# LPC_Rep.net
KiCad netlist of a schematic drawn in Altium Designer
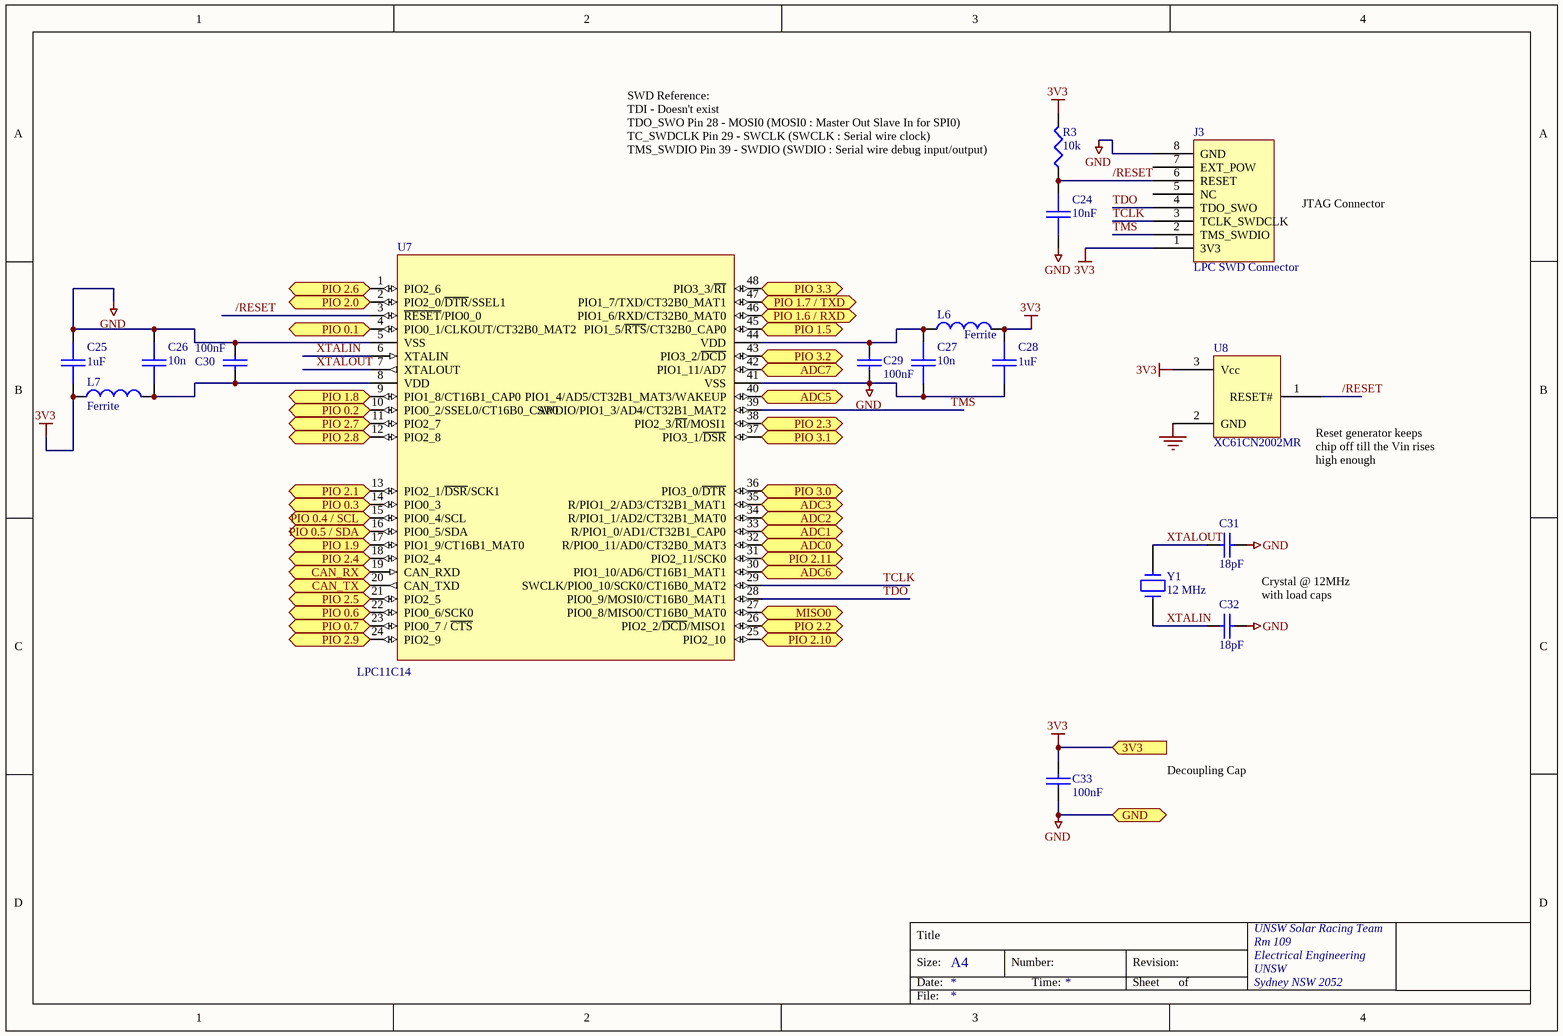
[diagram p0: LPC_Rep.SchDoc]

(export (version "E")
  (design (tool "Eeschema 10.0.6"))
  (components
    (comp (ref "C24")
      (value "10nF")
      (footprint "0603")
      (description "Capacitor")
      (libsource (lib "SunswiftLib20030312RR") (part "CAP"))
    )
    (comp (ref "C25")
      (value "1uF")
      (footprint "0603")
      (description "Capacitor")
      (fields (field (name "Comment") "1u"))
      (libsource (lib "RCLDQ") (part "CAP"))
    )
    (comp (ref "C26")
      (value "10n")
      (footprint "0603")
      (description "Capacitor")
      (libsource (lib "2009_BatteryMaster") (part "CAP"))
    )
    (comp (ref "C27")
      (value "10n")
      (footprint "0603")
      (description "Capacitor")
      (libsource (lib "2009_BatteryMaster") (part "CAP"))
    )
    (comp (ref "C28")
      (value "1uF")
      (footprint "0603")
      (description "Capacitor")
      (fields (field (name "Comment") "1u"))
      (libsource (lib "RCLDQ") (part "CAP"))
    )
    (comp (ref "C29")
      (value "100nF")
      (footprint "0603")
      (description "Capacitor")
      (libsource (lib "*") (part "CAP"))
    )
    (comp (ref "C30")
      (value "100nF")
      (footprint "0603")
      (description "Capacitor")
      (libsource (lib "*") (part "CAP"))
    )
    (comp (ref "C31")
      (value "18pF")
      (footprint "0603")
      (description "Capacitor")
      (libsource (lib "*") (part "CAP"))
    )
    (comp (ref "C32")
      (value "18pF")
      (footprint "0603")
      (description "Capacitor")
      (libsource (lib "*") (part "CAP"))
    )
    (comp (ref "C33")
      (value "100nF")
      (footprint "0603")
      (description "Capacitor")
      (libsource (lib "*") (part "CAP"))
    )
    (comp (ref "J3")
      (value "LPC SWD Connector")
      (footprint "IDC8")
      (libsource (lib "2009_BatteryMaster") (part "LPCLink_Connector"))
    )
    (comp (ref "L6")
      (value "Ferrite")
      (footprint "0603")
      (description "Inductor")
      (fields (field (name "MANUFACTURER") "Generic Components") (field (name "PUBLISHER") "Altium Limited"))
      (libsource (lib "RCLDQ") (part "INDUCTOR"))
    )
    (comp (ref "L7")
      (value "Ferrite")
      (footprint "0603")
      (description "Inductor")
      (fields (field (name "MANUFACTURER") "Generic Components") (field (name "PUBLISHER") "Altium Limited"))
      (libsource (lib "RCLDQ") (part "INDUCTOR"))
    )
    (comp (ref "R3")
      (value "10k")
      (footprint "0603")
      (description "Resistor")
      (libsource (lib "SunswiftLib20030312RR") (part "RES1"))
    )
    (comp (ref "U7")
      (value "LPC11C14")
      (footprint "TSQFP50P900X900-48N")
      (libsource (lib "LPC") (part "LPC11C14_Full"))
    )
    (comp (ref "U8")
      (value "XC61CN2002MR")
      (footprint "SOT23(3)")
      (description "SOT23 reset generator")
      (libsource (lib "*") (part "XC61F"))
    )
    (comp (ref "Y1")
      (value "12 MHz")
      (footprint "HC49/4H")
      (description "Crystal")
      (libsource (lib "*") (part "CRYSTAL"))
    )
  )
  (nets
    (net (code "1") (name "/ADC0") (class "Default")
      (node (ref "U7") (pin "32") (pinfunction "R/PIO0_11/AD0/CT32B0_MAT3_32") (pintype "bidirectional"))
    )
    (net (code "2") (name "/ADC1") (class "Default")
      (node (ref "U7") (pin "33") (pinfunction "R/PIO1_0/AD1/CT32B1_CAP0_33") (pintype "bidirectional"))
    )
    (net (code "3") (name "/ADC2") (class "Default")
      (node (ref "U7") (pin "34") (pinfunction "R/PIO1_1/AD2/CT32B1_MAT0_34") (pintype "bidirectional"))
    )
    (net (code "4") (name "/ADC3") (class "Default")
      (node (ref "U7") (pin "35") (pinfunction "R/PIO1_2/AD3/CT32B1_MAT1_35") (pintype "bidirectional"))
    )
    (net (code "5") (name "/ADC5") (class "Default")
      (node (ref "U7") (pin "40") (pinfunction "PIO1_4/AD5/CT32B1_MAT3/WAKEUP_40") (pintype "bidirectional"))
    )
    (net (code "6") (name "/ADC6") (class "Default")
      (node (ref "U7") (pin "30") (pinfunction "PIO1_10/AD6/CT16B1_MAT1_30") (pintype "bidirectional"))
    )
    (net (code "7") (name "/ADC7") (class "Default")
      (node (ref "U7") (pin "42") (pinfunction "PIO1_11/AD7_42") (pintype "bidirectional"))
    )
    (net (code "8") (name "/CAN_RX") (class "Default")
      (node (ref "U7") (pin "19") (pinfunction "CAN_RXD_19") (pintype "input"))
    )
    (net (code "9") (name "/CAN_TX") (class "Default")
      (node (ref "U7") (pin "20") (pinfunction "CAN_TXD_20") (pintype "output"))
    )
    (net (code "10") (name "/MISO0") (class "Default")
      (node (ref "U7") (pin "27") (pinfunction "PIO0_8/MISO0/CT16B0_MAT0_27") (pintype "bidirectional"))
    )
    (net (code "11") (name "/PIO 0.1") (class "Default")
      (node (ref "U7") (pin "4") (pinfunction "PIO0_1/CLKOUT/CT32B0_MAT2_4") (pintype "bidirectional"))
    )
    (net (code "12") (name "/PIO 0.2") (class "Default")
      (node (ref "U7") (pin "10") (pinfunction "PIO0_2/SSEL0/CT16B0_CAP0_10") (pintype "bidirectional"))
    )
    (net (code "13") (name "/PIO 0.3") (class "Default")
      (node (ref "U7") (pin "14") (pinfunction "PIO0_3_14") (pintype "bidirectional"))
    )
    (net (code "14") (name "/PIO 0.4 {slash} SCL") (class "Default")
      (node (ref "U7") (pin "15") (pinfunction "PIO0_4/SCL_15") (pintype "bidirectional"))
    )
    (net (code "15") (name "/PIO 0.5 {slash} SDA") (class "Default")
      (node (ref "U7") (pin "16") (pinfunction "PIO0_5/SDA_16") (pintype "bidirectional"))
    )
    (net (code "16") (name "/PIO 0.6") (class "Default")
      (node (ref "U7") (pin "22") (pinfunction "PIO0_6/SCK0_22") (pintype "bidirectional"))
    )
    (net (code "17") (name "/PIO 0.7") (class "Default")
      (node (ref "U7") (pin "23") (pinfunction "PIO0_7_/_~{CTS}_23") (pintype "bidirectional"))
    )
    (net (code "18") (name "/PIO 1.5") (class "Default")
      (node (ref "U7") (pin "45") (pinfunction "PIO1_5/~{RTS}/CT32B0_CAP0_45") (pintype "bidirectional"))
    )
    (net (code "19") (name "/PIO 1.6 {slash} RXD") (class "Default")
      (node (ref "U7") (pin "46") (pinfunction "PIO1_6/RXD/CT32B0_MAT0_46") (pintype "bidirectional"))
    )
    (net (code "20") (name "/PIO 1.7 {slash} TXD") (class "Default")
      (node (ref "U7") (pin "47") (pinfunction "PIO1_7/TXD/CT32B0_MAT1_47") (pintype "bidirectional"))
    )
    (net (code "21") (name "/PIO 1.8") (class "Default")
      (node (ref "U7") (pin "9") (pinfunction "PIO1_8/CT16B1_CAP0_9") (pintype "bidirectional"))
    )
    (net (code "22") (name "/PIO 1.9") (class "Default")
      (node (ref "U7") (pin "17") (pinfunction "PIO1_9/CT16B1_MAT0_17") (pintype "bidirectional"))
    )
    (net (code "23") (name "/PIO 2.0") (class "Default")
      (node (ref "U7") (pin "2") (pinfunction "PIO2_0/~{DTR}/SSEL1_2") (pintype "bidirectional"))
    )
    (net (code "24") (name "/PIO 2.1") (class "Default")
      (node (ref "U7") (pin "13") (pinfunction "PIO2_1/~{DSR}/SCK1_13") (pintype "bidirectional"))
    )
    (net (code "25") (name "/PIO 2.2") (class "Default")
      (node (ref "U7") (pin "26") (pinfunction "PIO2_2/~{DCD}/MISO1_26") (pintype "bidirectional"))
    )
    (net (code "26") (name "/PIO 2.3") (class "Default")
      (node (ref "U7") (pin "38") (pinfunction "PIO2_3/~{RI}/MOSI1_38") (pintype "bidirectional"))
    )
    (net (code "27") (name "/PIO 2.4") (class "Default")
      (node (ref "U7") (pin "18") (pinfunction "PIO2_4_18") (pintype "bidirectional"))
    )
    (net (code "28") (name "/PIO 2.5") (class "Default")
      (node (ref "U7") (pin "21") (pinfunction "PIO2_5_21") (pintype "bidirectional"))
    )
    (net (code "29") (name "/PIO 2.6") (class "Default")
      (node (ref "U7") (pin "1") (pinfunction "PIO2_6_1") (pintype "bidirectional"))
    )
    (net (code "30") (name "/PIO 2.7") (class "Default")
      (node (ref "U7") (pin "11") (pinfunction "PIO2_7_11") (pintype "bidirectional"))
    )
    (net (code "31") (name "/PIO 2.8") (class "Default")
      (node (ref "U7") (pin "12") (pinfunction "PIO2_8_12") (pintype "bidirectional"))
    )
    (net (code "32") (name "/PIO 2.9") (class "Default")
      (node (ref "U7") (pin "24") (pinfunction "PIO2_9_24") (pintype "bidirectional"))
    )
    (net (code "33") (name "/PIO 2.10") (class "Default")
      (node (ref "U7") (pin "25") (pinfunction "PIO2_10_25") (pintype "bidirectional"))
    )
    (net (code "34") (name "/PIO 2.11") (class "Default")
      (node (ref "U7") (pin "31") (pinfunction "PIO2_11/SCK0_31") (pintype "bidirectional"))
    )
    (net (code "35") (name "/PIO 3.0") (class "Default")
      (node (ref "U7") (pin "36") (pinfunction "PIO3_0/~{DTR}_36") (pintype "bidirectional"))
    )
    (net (code "36") (name "/PIO 3.1") (class "Default")
      (node (ref "U7") (pin "37") (pinfunction "PIO3_1/~{DSR}_37") (pintype "bidirectional"))
    )
    (net (code "37") (name "/PIO 3.2") (class "Default")
      (node (ref "U7") (pin "43") (pinfunction "PIO3_2/~{DCD}_43") (pintype "bidirectional"))
    )
    (net (code "38") (name "/PIO 3.3") (class "Default")
      (node (ref "U7") (pin "48") (pinfunction "PIO3_3/~{RI}_48") (pintype "bidirectional"))
    )
    (net (code "39") (name "/TCLK") (class "Default")
      (node (ref "J3") (pin "3") (pinfunction "TCLK_SWDCLK_3") (pintype "passive"))
      (node (ref "U7") (pin "29") (pinfunction "SWCLK/PIO0_10/SCK0/CT16B0_MAT2_29") (pintype "bidirectional"))
    )
    (net (code "40") (name "/TDO") (class "Default")
      (node (ref "J3") (pin "4") (pinfunction "TDO_SWO_4") (pintype "passive"))
      (node (ref "U7") (pin "28") (pinfunction "PIO0_9/MOSI0/CT16B0_MAT1_28") (pintype "bidirectional"))
    )
    (net (code "41") (name "/TMS") (class "Default")
      (node (ref "J3") (pin "2") (pinfunction "TMS_SWDIO_2") (pintype "passive"))
      (node (ref "U7") (pin "39") (pinfunction "SWDIO/PIO1_3/AD4/CT32B1_MAT2_39") (pintype "bidirectional"))
    )
    (net (code "42") (name "/XTALIN") (class "Default")
      (node (ref "C32") (pin "1") (pinfunction "1_1") (pintype "passive"))
      (node (ref "U7") (pin "6") (pinfunction "XTALIN_6") (pintype "input"))
      (node (ref "Y1") (pin "1") (pinfunction "1_1") (pintype "passive"))
    )
    (net (code "43") (name "/XTALOUT") (class "Default")
      (node (ref "C31") (pin "1") (pinfunction "1_1") (pintype "passive"))
      (node (ref "U7") (pin "7") (pinfunction "XTALOUT_7") (pintype "output"))
      (node (ref "Y1") (pin "2") (pinfunction "2_2") (pintype "passive"))
    )
    (net (code "44") (name "/{slash}RESET") (class "Default")
      (node (ref "C24") (pin "1") (pinfunction "1_1") (pintype "passive"))
      (node (ref "J3") (pin "6") (pinfunction "RESET_6") (pintype "passive"))
      (node (ref "R3") (pin "1") (pinfunction "1_1") (pintype "passive"))
      (node (ref "U7") (pin "3") (pinfunction "~{RESET}/PIO0_0_3") (pintype "bidirectional"))
      (node (ref "U8") (pin "1") (pinfunction "RESET#_1") (pintype "passive"))
    )
    (net (code "45") (name "3V3") (class "Default")
      (node (ref "C25") (pin "2") (pinfunction "2_2") (pintype "passive"))
      (node (ref "C28") (pin "1") (pinfunction "1_1") (pintype "passive"))
      (node (ref "C33") (pin "1") (pinfunction "1_1") (pintype "passive"))
      (node (ref "J3") (pin "1") (pinfunction "3V3_1") (pintype "passive"))
      (node (ref "L6") (pin "2") (pinfunction "2_2") (pintype "passive"))
      (node (ref "L7") (pin "1") (pinfunction "1_1") (pintype "passive"))
      (node (ref "R3") (pin "2") (pinfunction "2_2") (pintype "passive"))
      (node (ref "U8") (pin "3") (pinfunction "Vcc_3") (pintype "passive"))
    )
    (net (code "46") (name "GND") (class "Default")
      (node (ref "C24") (pin "2") (pinfunction "2_2") (pintype "passive"))
      (node (ref "C25") (pin "1") (pinfunction "1_1") (pintype "passive"))
      (node (ref "C26") (pin "1") (pinfunction "1_1") (pintype "passive"))
      (node (ref "C27") (pin "2") (pinfunction "2_2") (pintype "passive"))
      (node (ref "C28") (pin "2") (pinfunction "2_2") (pintype "passive"))
      (node (ref "C29") (pin "2") (pinfunction "2_2") (pintype "passive"))
      (node (ref "C30") (pin "1") (pinfunction "1_1") (pintype "passive"))
      (node (ref "C31") (pin "2") (pinfunction "2_2") (pintype "passive"))
      (node (ref "C32") (pin "2") (pinfunction "2_2") (pintype "passive"))
      (node (ref "C33") (pin "2") (pinfunction "2_2") (pintype "passive"))
      (node (ref "J3") (pin "8") (pinfunction "GND_8") (pintype "passive"))
      (node (ref "U7") (pin "41") (pinfunction "VSS_41") (pintype "power_in"))
      (node (ref "U7") (pin "5") (pinfunction "VSS_5") (pintype "power_in"))
      (node (ref "U8") (pin "2") (pinfunction "GND_2") (pintype "passive"))
    )
    (net (code "47") (name "Net-(C26-Pad2)") (class "Default")
      (node (ref "C26") (pin "2") (pinfunction "2_2") (pintype "passive"))
      (node (ref "C30") (pin "2") (pinfunction "2_2") (pintype "passive"))
      (node (ref "L7") (pin "2") (pinfunction "2_2") (pintype "passive"))
      (node (ref "U7") (pin "8") (pinfunction "VDD_8") (pintype "power_in"))
    )
    (net (code "48") (name "Net-(C27-Pad1)") (class "Default")
      (node (ref "C27") (pin "1") (pinfunction "1_1") (pintype "passive"))
      (node (ref "C29") (pin "1") (pinfunction "1_1") (pintype "passive"))
      (node (ref "L6") (pin "1") (pinfunction "1_1") (pintype "passive"))
      (node (ref "U7") (pin "44") (pinfunction "VDD_44") (pintype "power_in"))
    )
    (net (code "49") (name "unconnected-(J3-EXT_POW-Pad7)") (class "Default")
      (node (ref "J3") (pin "7") (pinfunction "EXT_POW_7") (pintype "passive"))
    )
    (net (code "50") (name "unconnected-(J3-NC-Pad5)") (class "Default")
      (node (ref "J3") (pin "5") (pinfunction "NC_5") (pintype "passive"))
    )
  )
)
